# PMIC.net
KiCad netlist of a schematic drawn in Altium Designer
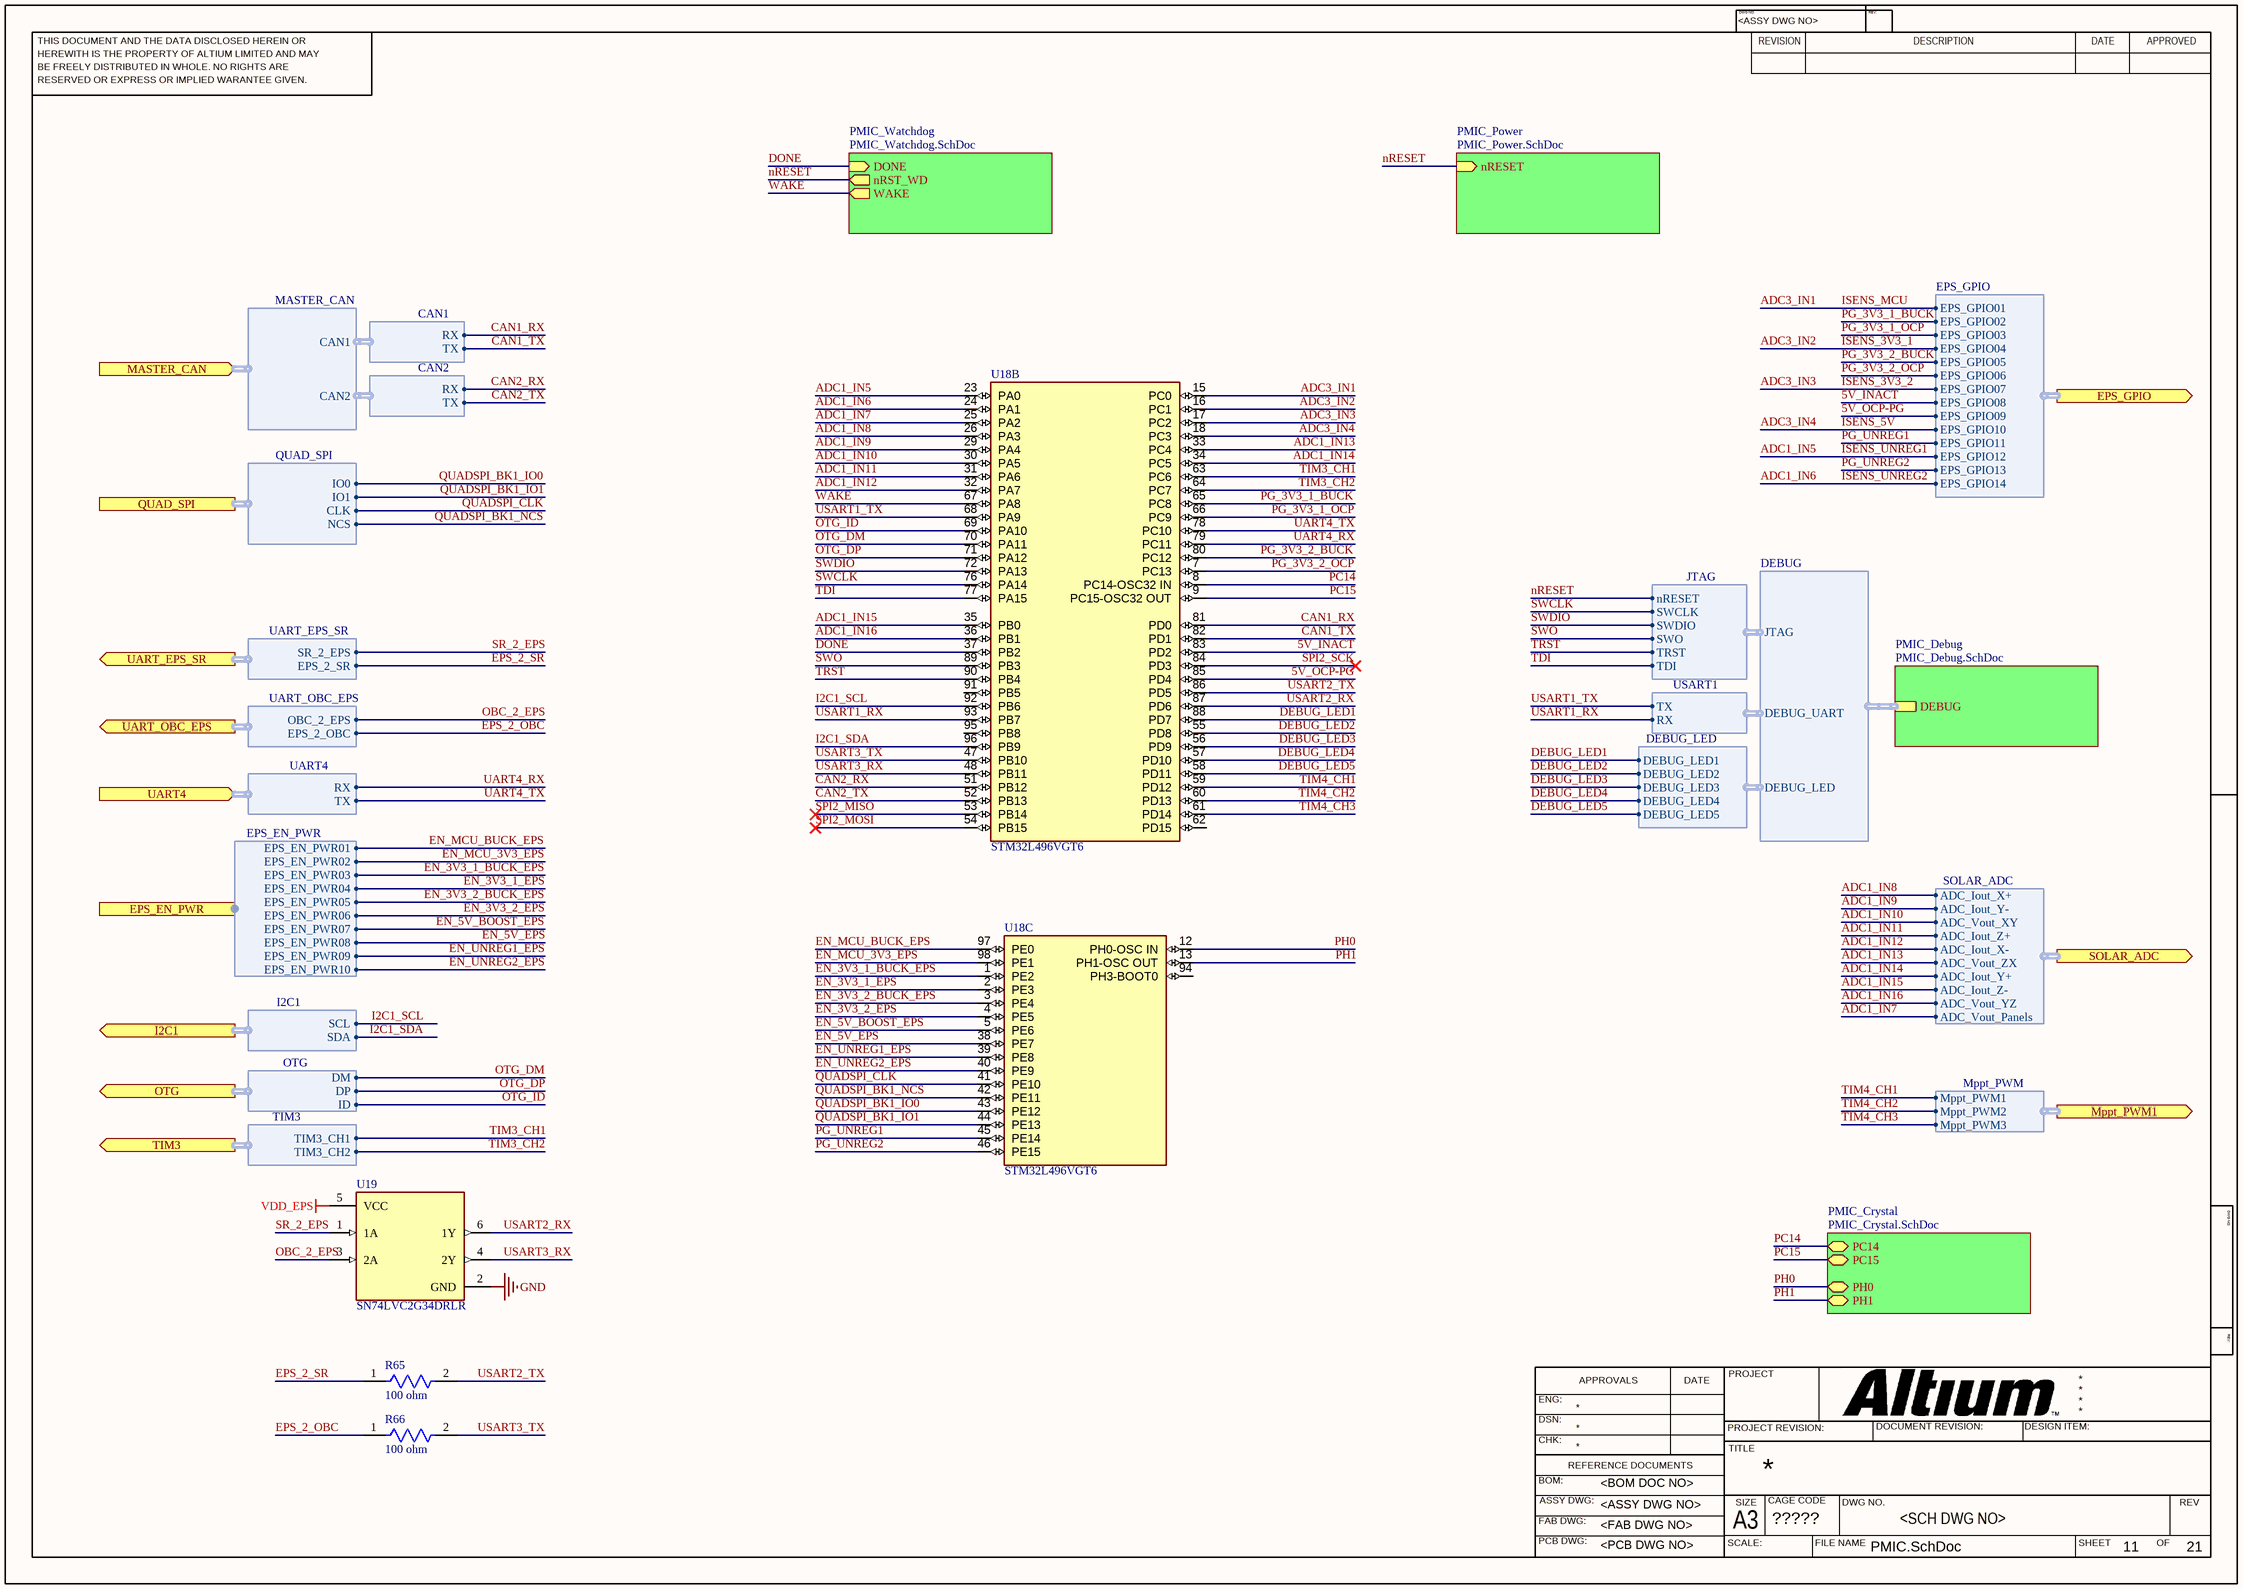
[diagram p0: PMIC.SchDoc]

(export (version "E")
  (design (tool "Eeschema 10.0.6"))
  (components
    (comp (ref "R65")
      (value "100 ohm")
      (footprint "FP-ERJP03-MFG")
      (description "ERJ-P03F1000V SMD Chip Resistor, 100 Ohm, ± 1%, 200 mW, 0603 [1608 Metric], Thick Film, Anti-Surge")
      (fields (field (name "TOLERANCE") "1%"))
      (libsource (lib "Altium Content Vault") (part "1029c3af85768c4190bb7ad29bc67b5"))
    )
    (comp (ref "R66")
      (value "100 ohm")
      (footprint "FP-ERJP03-MFG")
      (description "ERJ-P03F1000V SMD Chip Resistor, 100 Ohm, ± 1%, 200 mW, 0603 [1608 Metric], Thick Film, Anti-Surge")
      (fields (field (name "TOLERANCE") "1%"))
      (libsource (lib "Altium Content Vault") (part "1029c3af85768c4190bb7ad29bc67b5"))
    )
    (comp (ref "U18")
      (value "STM32L496VGT6")
      (footprint "FP-LQFP100-1L-MFG")
      (description "IC MCU 32BIT 1MB FLASH 100LQFP")
      (fields
        (field (name "MANUFACTURER") "STMicroelectronics")
        (field (name "OCTOPART") "https://octopart.com/stm32l496vgt6-stmicroelectronics-80826723")
      )
      (libsource (lib "Altium Content Vault") (part "c3654b0af0513536dfc3423c68ccd0e"))
    )
    (comp (ref "U19")
      (value "SN74LVC2G34DRLR")
      (footprint "FP-DRL0006A-MFG")
      (description "IC BUFFER NON-INVERT 5.5V 6SOT")
      (libsource (lib "Altium Content Vault") (part "59303bce76f5fafbc101ba271662c75"))
    )
  )
  (nets
    (net (code "19") (name "/5V_INACT") (class "Default")
      (node (ref "U18") (pin "83") (pinfunction "PD2_83") (pintype "bidirectional"))
    )
    (net (code "20") (name "/5V_OCP-PG") (class "Default")
      (node (ref "U18") (pin "85") (pinfunction "PD4_85") (pintype "bidirectional"))
    )
    (net (code "21") (name "/ADC1_IN5") (class "Default")
      (node (ref "U18") (pin "23") (pinfunction "PA0_23") (pintype "bidirectional"))
    )
    (net (code "22") (name "/ADC1_IN6") (class "Default")
      (node (ref "U18") (pin "24") (pinfunction "PA1_24") (pintype "bidirectional"))
    )
    (net (code "23") (name "/ADC1_IN7") (class "Default")
      (node (ref "U18") (pin "25") (pinfunction "PA2_25") (pintype "bidirectional"))
    )
    (net (code "24") (name "/ADC1_IN8") (class "Default")
      (node (ref "U18") (pin "26") (pinfunction "PA3_26") (pintype "bidirectional"))
    )
    (net (code "25") (name "/ADC1_IN9") (class "Default")
      (node (ref "U18") (pin "29") (pinfunction "PA4_29") (pintype "bidirectional"))
    )
    (net (code "26") (name "/ADC1_IN10") (class "Default")
      (node (ref "U18") (pin "30") (pinfunction "PA5_30") (pintype "bidirectional"))
    )
    (net (code "27") (name "/ADC1_IN11") (class "Default")
      (node (ref "U18") (pin "31") (pinfunction "PA6_31") (pintype "bidirectional"))
    )
    (net (code "28") (name "/ADC1_IN12") (class "Default")
      (node (ref "U18") (pin "32") (pinfunction "PA7_32") (pintype "bidirectional"))
    )
    (net (code "29") (name "/ADC1_IN13") (class "Default")
      (node (ref "U18") (pin "33") (pinfunction "PC4_33") (pintype "bidirectional"))
    )
    (net (code "30") (name "/ADC1_IN14") (class "Default")
      (node (ref "U18") (pin "34") (pinfunction "PC5_34") (pintype "bidirectional"))
    )
    (net (code "31") (name "/ADC1_IN15") (class "Default")
      (node (ref "U18") (pin "35") (pinfunction "PB0_35") (pintype "bidirectional"))
    )
    (net (code "32") (name "/ADC1_IN16") (class "Default")
      (node (ref "U18") (pin "36") (pinfunction "PB1_36") (pintype "bidirectional"))
    )
    (net (code "33") (name "/ADC3_IN1") (class "Default")
      (node (ref "U18") (pin "15") (pinfunction "PC0_15") (pintype "bidirectional"))
    )
    (net (code "34") (name "/ADC3_IN2") (class "Default")
      (node (ref "U18") (pin "16") (pinfunction "PC1_16") (pintype "bidirectional"))
    )
    (net (code "35") (name "/ADC3_IN3") (class "Default")
      (node (ref "U18") (pin "17") (pinfunction "PC2_17") (pintype "bidirectional"))
    )
    (net (code "36") (name "/ADC3_IN4") (class "Default")
      (node (ref "U18") (pin "18") (pinfunction "PC3_18") (pintype "bidirectional"))
    )
    (net (code "37") (name "/CAN1_RX") (class "Default")
      (node (ref "U18") (pin "81") (pinfunction "PD0_81") (pintype "bidirectional"))
    )
    (net (code "38") (name "/CAN1_TX") (class "Default")
      (node (ref "U18") (pin "82") (pinfunction "PD1_82") (pintype "bidirectional"))
    )
    (net (code "39") (name "/CAN2_RX") (class "Default")
      (node (ref "U18") (pin "51") (pinfunction "PB12_51") (pintype "bidirectional"))
    )
    (net (code "40") (name "/CAN2_TX") (class "Default")
      (node (ref "U18") (pin "52") (pinfunction "PB13_52") (pintype "bidirectional"))
    )
    (net (code "41") (name "/DEBUG_LED1") (class "Default")
      (node (ref "U18") (pin "88") (pinfunction "PD7_88") (pintype "bidirectional"))
    )
    (net (code "42") (name "/DEBUG_LED2") (class "Default")
      (node (ref "U18") (pin "55") (pinfunction "PD8_55") (pintype "bidirectional"))
    )
    (net (code "43") (name "/DEBUG_LED3") (class "Default")
      (node (ref "U18") (pin "56") (pinfunction "PD9_56") (pintype "bidirectional"))
    )
    (net (code "44") (name "/DEBUG_LED4") (class "Default")
      (node (ref "U18") (pin "57") (pinfunction "PD10_57") (pintype "bidirectional"))
    )
    (net (code "45") (name "/DEBUG_LED5") (class "Default")
      (node (ref "U18") (pin "58") (pinfunction "PD11_58") (pintype "bidirectional"))
    )
    (net (code "46") (name "/DONE") (class "Default")
      (node (ref "U18") (pin "37") (pinfunction "PB2_37") (pintype "bidirectional"))
    )
    (net (code "47") (name "/EN_3V3_1_BUCK_EPS") (class "Default")
      (node (ref "U18") (pin "1") (pinfunction "PE2_1") (pintype "bidirectional"))
    )
    (net (code "48") (name "/EN_3V3_1_EPS") (class "Default")
      (node (ref "U18") (pin "2") (pinfunction "PE3_2") (pintype "bidirectional"))
    )
    (net (code "49") (name "/EN_3V3_2_BUCK_EPS") (class "Default")
      (node (ref "U18") (pin "3") (pinfunction "PE4_3") (pintype "bidirectional"))
    )
    (net (code "50") (name "/EN_3V3_2_EPS") (class "Default")
      (node (ref "U18") (pin "4") (pinfunction "PE5_4") (pintype "bidirectional"))
    )
    (net (code "51") (name "/EN_5V_BOOST_EPS") (class "Default")
      (node (ref "U18") (pin "5") (pinfunction "PE6_5") (pintype "bidirectional"))
    )
    (net (code "52") (name "/EN_5V_EPS") (class "Default")
      (node (ref "U18") (pin "38") (pinfunction "PE7_38") (pintype "bidirectional"))
    )
    (net (code "53") (name "/EN_MCU_3V3_EPS") (class "Default")
      (node (ref "U18") (pin "98") (pinfunction "PE1_98") (pintype "bidirectional"))
    )
    (net (code "54") (name "/EN_MCU_BUCK_EPS") (class "Default")
      (node (ref "U18") (pin "97") (pinfunction "PE0_97") (pintype "bidirectional"))
    )
    (net (code "55") (name "/EN_UNREG1_EPS") (class "Default")
      (node (ref "U18") (pin "39") (pinfunction "PE8_39") (pintype "bidirectional"))
    )
    (net (code "56") (name "/EN_UNREG2_EPS") (class "Default")
      (node (ref "U18") (pin "40") (pinfunction "PE9_40") (pintype "bidirectional"))
    )
    (net (code "57") (name "/EPS_2_OBC") (class "Default")
      (node (ref "R66") (pin "1") (pinfunction "1_1") (pintype "passive"))
    )
    (net (code "58") (name "/EPS_2_SR") (class "Default")
      (node (ref "R65") (pin "1") (pinfunction "1_1") (pintype "passive"))
    )
    (net (code "59") (name "/I2C1_SCL") (class "Default")
      (node (ref "U18") (pin "92") (pinfunction "PB6_92") (pintype "bidirectional"))
    )
    (net (code "60") (name "/I2C1_SDA") (class "Default")
      (node (ref "U18") (pin "96") (pinfunction "PB9_96") (pintype "bidirectional"))
    )
    (net (code "62") (name "/OBC_2_EPS") (class "Default")
      (node (ref "U19") (pin "3") (pinfunction "2A_3") (pintype "input"))
    )
    (net (code "63") (name "/OTG_DM") (class "Default")
      (node (ref "U18") (pin "70") (pinfunction "PA11_70") (pintype "bidirectional"))
    )
    (net (code "64") (name "/OTG_DP") (class "Default")
      (node (ref "U18") (pin "71") (pinfunction "PA12_71") (pintype "bidirectional"))
    )
    (net (code "65") (name "/OTG_ID") (class "Default")
      (node (ref "U18") (pin "69") (pinfunction "PA10_69") (pintype "bidirectional"))
    )
    (net (code "66") (name "/PC14") (class "Default")
      (node (ref "U18") (pin "8") (pinfunction "PC14-OSC32_IN_8") (pintype "bidirectional"))
    )
    (net (code "67") (name "/PC15") (class "Default")
      (node (ref "U18") (pin "9") (pinfunction "PC15-OSC32_OUT_9") (pintype "bidirectional"))
    )
    (net (code "68") (name "/PG_3V3_1_BUCK") (class "Default")
      (node (ref "U18") (pin "65") (pinfunction "PC8_65") (pintype "bidirectional"))
    )
    (net (code "69") (name "/PG_3V3_1_OCP") (class "Default")
      (node (ref "U18") (pin "66") (pinfunction "PC9_66") (pintype "bidirectional"))
    )
    (net (code "70") (name "/PG_3V3_2_BUCK") (class "Default")
      (node (ref "U18") (pin "80") (pinfunction "PC12_80") (pintype "bidirectional"))
    )
    (net (code "71") (name "/PG_3V3_2_OCP") (class "Default")
      (node (ref "U18") (pin "7") (pinfunction "PC13_7") (pintype "bidirectional"))
    )
    (net (code "72") (name "/PG_UNREG1") (class "Default")
      (node (ref "U18") (pin "45") (pinfunction "PE14_45") (pintype "bidirectional"))
    )
    (net (code "73") (name "/PG_UNREG2") (class "Default")
      (node (ref "U18") (pin "46") (pinfunction "PE15_46") (pintype "bidirectional"))
    )
    (net (code "74") (name "/PH0") (class "Default")
      (node (ref "U18") (pin "12") (pinfunction "PH0-OSC_IN_12") (pintype "bidirectional"))
    )
    (net (code "75") (name "/PH1") (class "Default")
      (node (ref "U18") (pin "13") (pinfunction "PH1-OSC_OUT_13") (pintype "bidirectional"))
    )
    (net (code "76") (name "/QUADSPI_BK1_IO0") (class "Default")
      (node (ref "U18") (pin "43") (pinfunction "PE12_43") (pintype "bidirectional"))
    )
    (net (code "77") (name "/QUADSPI_BK1_IO1") (class "Default")
      (node (ref "U18") (pin "44") (pinfunction "PE13_44") (pintype "bidirectional"))
    )
    (net (code "78") (name "/QUADSPI_BK1_NCS") (class "Default")
      (node (ref "U18") (pin "42") (pinfunction "PE11_42") (pintype "bidirectional"))
    )
    (net (code "79") (name "/QUADSPI_CLK") (class "Default")
      (node (ref "U18") (pin "41") (pinfunction "PE10_41") (pintype "bidirectional"))
    )
    (net (code "80") (name "/SPI2_MISO") (class "Default")
      (node (ref "U18") (pin "53") (pinfunction "PB14_53") (pintype "bidirectional+no_connect"))
    )
    (net (code "81") (name "/SPI2_MOSI") (class "Default")
      (node (ref "U18") (pin "54") (pinfunction "PB15_54") (pintype "bidirectional+no_connect"))
    )
    (net (code "82") (name "/SPI2_SCK") (class "Default")
      (node (ref "U18") (pin "84") (pinfunction "PD3_84") (pintype "bidirectional+no_connect"))
    )
    (net (code "83") (name "/SR_2_EPS") (class "Default")
      (node (ref "U19") (pin "1") (pinfunction "1A_1") (pintype "input"))
    )
    (net (code "84") (name "/SWCLK") (class "Default")
      (node (ref "U18") (pin "76") (pinfunction "PA14_76") (pintype "bidirectional"))
    )
    (net (code "85") (name "/SWDIO") (class "Default")
      (node (ref "U18") (pin "72") (pinfunction "PA13_72") (pintype "bidirectional"))
    )
    (net (code "86") (name "/SWO") (class "Default")
      (node (ref "U18") (pin "89") (pinfunction "PB3_89") (pintype "bidirectional"))
    )
    (net (code "87") (name "/TDI") (class "Default")
      (node (ref "U18") (pin "77") (pinfunction "PA15_77") (pintype "bidirectional"))
    )
    (net (code "88") (name "/TIM3_CH1") (class "Default")
      (node (ref "U18") (pin "63") (pinfunction "PC6_63") (pintype "bidirectional"))
    )
    (net (code "89") (name "/TIM3_CH2") (class "Default")
      (node (ref "U18") (pin "64") (pinfunction "PC7_64") (pintype "bidirectional"))
    )
    (net (code "90") (name "/TIM4_CH1") (class "Default")
      (node (ref "U18") (pin "59") (pinfunction "PD12_59") (pintype "bidirectional"))
    )
    (net (code "91") (name "/TIM4_CH2") (class "Default")
      (node (ref "U18") (pin "60") (pinfunction "PD13_60") (pintype "bidirectional"))
    )
    (net (code "92") (name "/TIM4_CH3") (class "Default")
      (node (ref "U18") (pin "61") (pinfunction "PD14_61") (pintype "bidirectional"))
    )
    (net (code "93") (name "/TRST") (class "Default")
      (node (ref "U18") (pin "90") (pinfunction "PB4_90") (pintype "bidirectional"))
    )
    (net (code "94") (name "/UART4_RX") (class "Default")
      (node (ref "U18") (pin "79") (pinfunction "PC11_79") (pintype "bidirectional"))
    )
    (net (code "95") (name "/UART4_TX") (class "Default")
      (node (ref "U18") (pin "78") (pinfunction "PC10_78") (pintype "bidirectional"))
    )
    (net (code "96") (name "/USART1_RX") (class "Default")
      (node (ref "U18") (pin "93") (pinfunction "PB7_93") (pintype "bidirectional"))
    )
    (net (code "97") (name "/USART1_TX") (class "Default")
      (node (ref "U18") (pin "68") (pinfunction "PA9_68") (pintype "bidirectional"))
    )
    (net (code "98") (name "/USART2_RX") (class "Default")
      (node (ref "U18") (pin "87") (pinfunction "PD6_87") (pintype "bidirectional"))
      (node (ref "U19") (pin "6") (pinfunction "1Y_6") (pintype "output"))
    )
    (net (code "99") (name "/USART2_TX") (class "Default")
      (node (ref "R65") (pin "2") (pinfunction "2_2") (pintype "passive"))
      (node (ref "U18") (pin "86") (pinfunction "PD5_86") (pintype "bidirectional"))
    )
    (net (code "100") (name "/USART3_RX") (class "Default")
      (node (ref "U18") (pin "48") (pinfunction "PB11_48") (pintype "bidirectional"))
      (node (ref "U19") (pin "4") (pinfunction "2Y_4") (pintype "output"))
    )
    (net (code "101") (name "/USART3_TX") (class "Default")
      (node (ref "R66") (pin "2") (pinfunction "2_2") (pintype "passive"))
      (node (ref "U18") (pin "47") (pinfunction "PB10_47") (pintype "bidirectional"))
    )
    (net (code "102") (name "/WAKE") (class "Default")
      (node (ref "U18") (pin "67") (pinfunction "PA8_67") (pintype "bidirectional"))
    )
    (net (code "121") (name "GND") (class "Default")
      (node (ref "U19") (pin "2") (pinfunction "GND_2") (pintype "power_in"))
    )
    (net (code "122") (name "VDD_EPS") (class "Default")
      (node (ref "U19") (pin "5") (pinfunction "VCC_5") (pintype "power_in"))
    )
    (net (code "123") (name "unconnected-(U18B-PB5-Pad91)") (class "Default")
      (node (ref "U18") (pin "91") (pinfunction "PB5_91") (pintype "bidirectional"))
    )
    (net (code "124") (name "unconnected-(U18B-PB8-Pad95)") (class "Default")
      (node (ref "U18") (pin "95") (pinfunction "PB8_95") (pintype "bidirectional"))
    )
    (net (code "125") (name "unconnected-(U18B-PD15-Pad62)") (class "Default")
      (node (ref "U18") (pin "62") (pinfunction "PD15_62") (pintype "bidirectional"))
    )
    (net (code "126") (name "unconnected-(U18C-PH3-BOOT0-Pad94)") (class "Default")
      (node (ref "U18") (pin "94") (pinfunction "PH3-BOOT0_94") (pintype "bidirectional"))
    )
  )
)
